# CAN0.net
KiCad netlist of a schematic drawn in Altium Designer
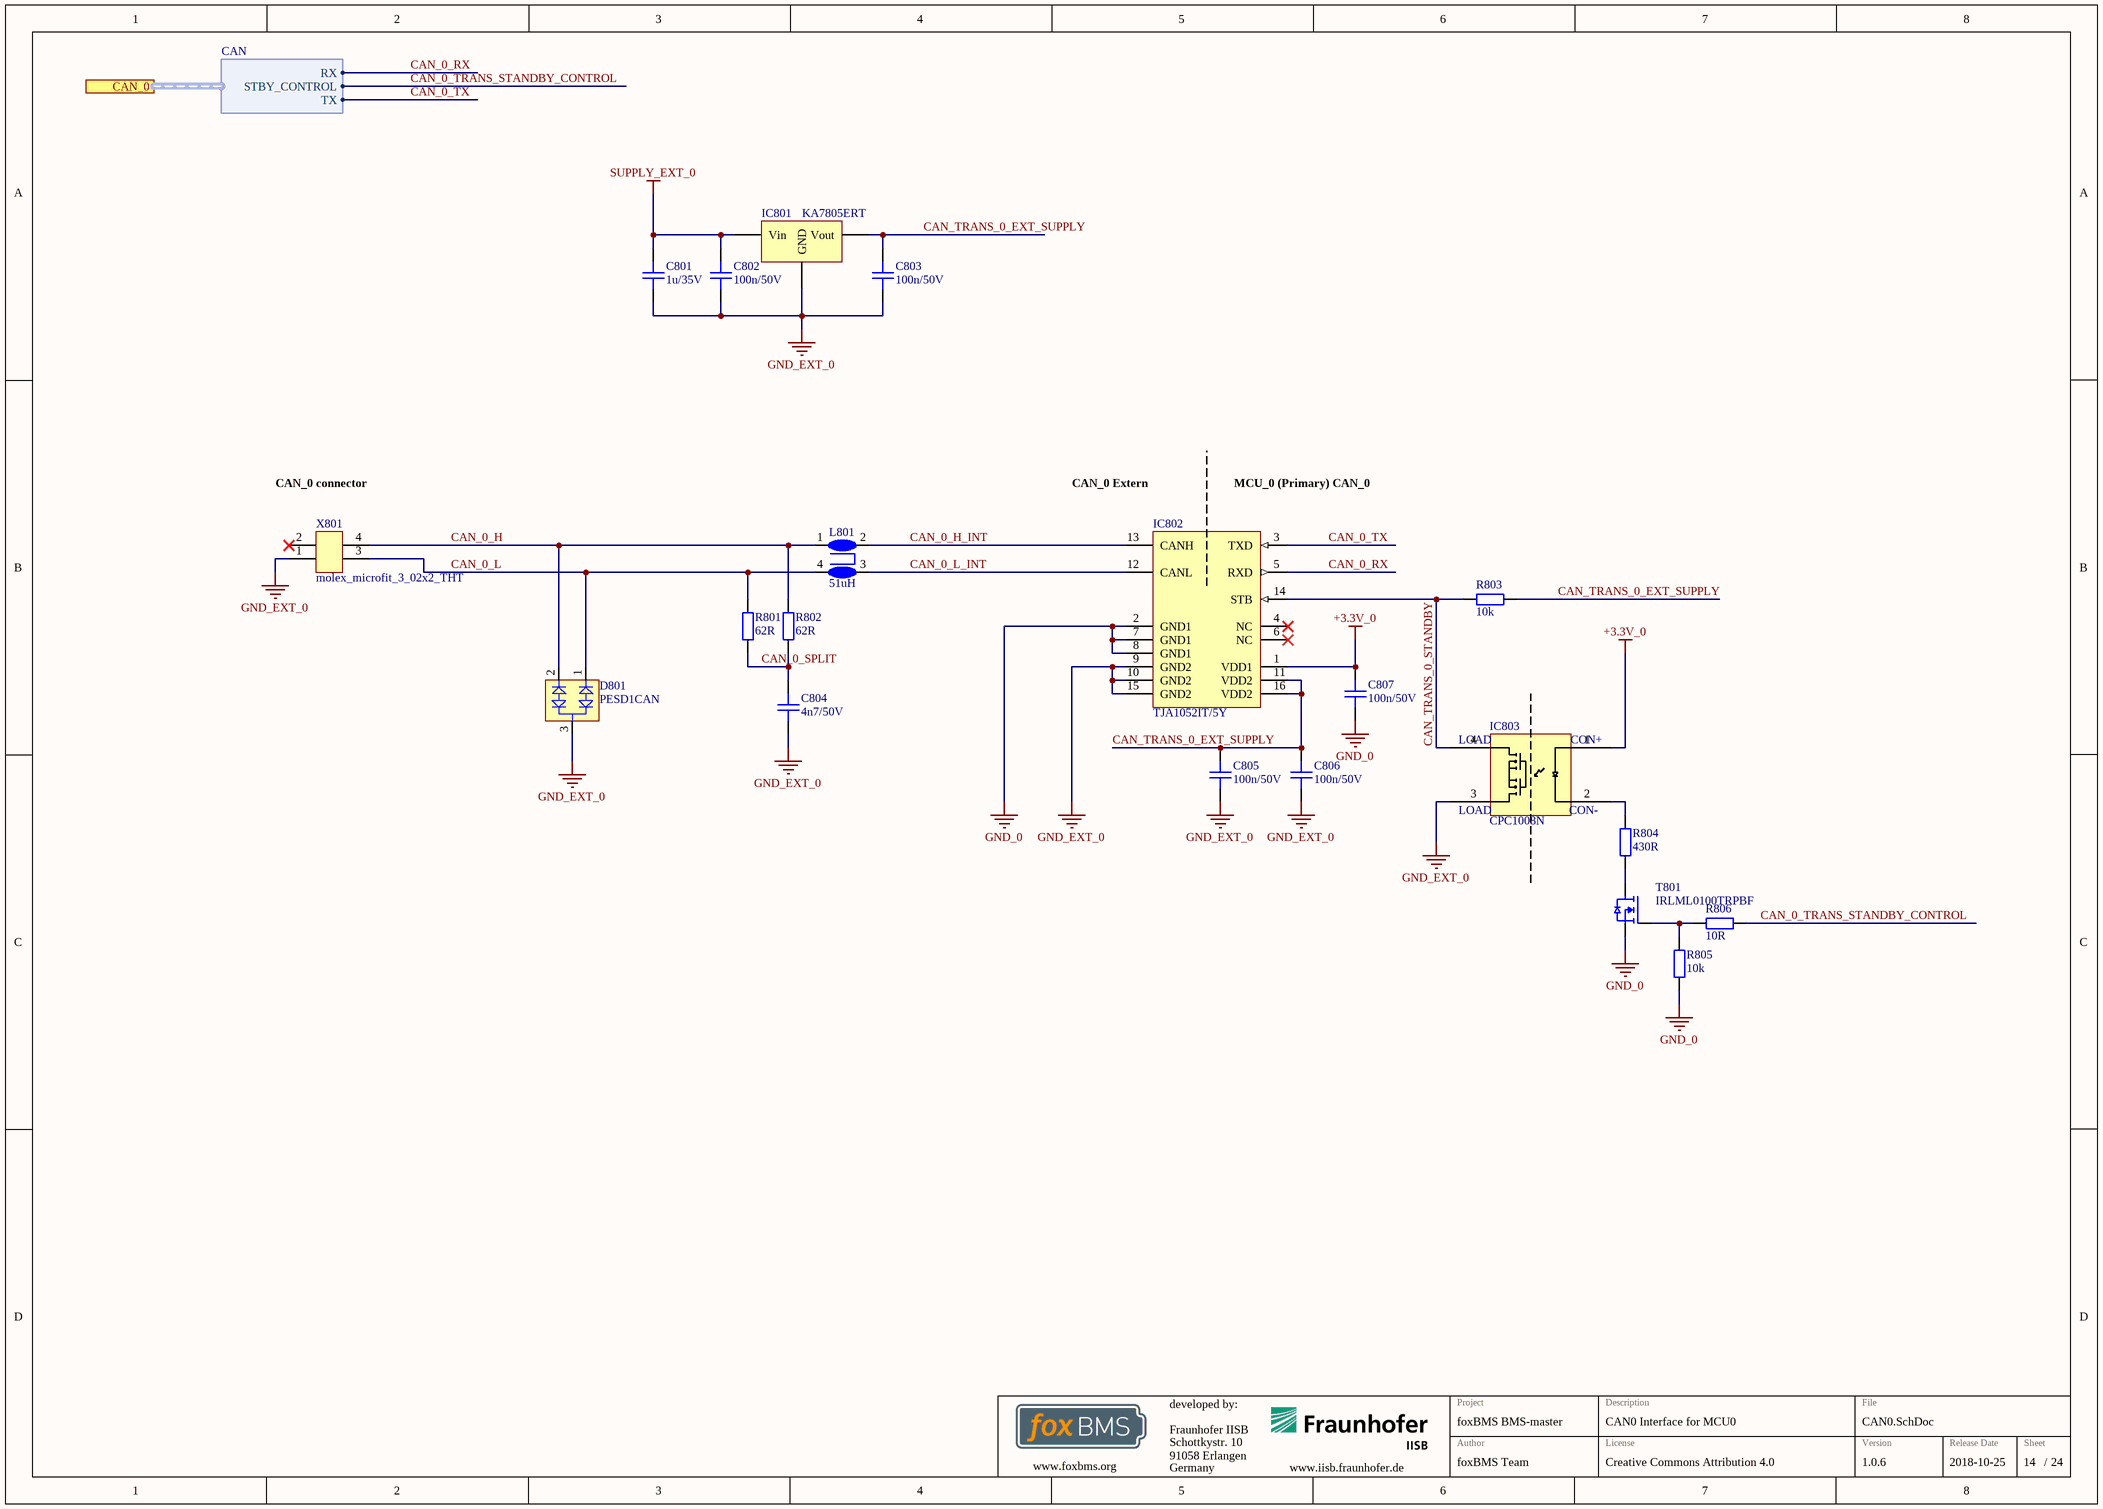
[diagram p0: CAN0.SchDoc]

(export (version "E")
  (design (tool "Eeschema 10.0.6"))
  (components
    (comp (ref "C801")
      (value "1u/35V")
      (footprint "CAPC1608X08N")
      (description "MLCC")
      (fields (field (name "PART NUMBER") "gen_C_ceramic_1u_35V_X7R_0603"))
      (libsource (lib "OE750") (part "C"))
    )
    (comp (ref "C802")
      (value "100n/50V")
      (footprint "CAPC1608X08N")
      (description "MLCC")
      (fields (field (name "PART NUMBER") "gen_C_ceramic_100n_50V_X7R_0603"))
      (libsource (lib "OE750") (part "C"))
    )
    (comp (ref "C803")
      (value "100n/50V")
      (footprint "CAPC1608X08N")
      (description "MLCC")
      (fields (field (name "PART NUMBER") "gen_C_ceramic_100n_50V_X7R_0603"))
      (libsource (lib "OE750") (part "C"))
    )
    (comp (ref "C804")
      (value "4n7/50V")
      (footprint "CAPC1608X08N")
      (description "MLCC")
      (fields (field (name "PART NUMBER") "gen_C_ceramic_4n7_50V_X7R_0603"))
      (libsource (lib "OE750") (part "C"))
    )
    (comp (ref "C805")
      (value "100n/50V")
      (footprint "CAPC1608X08N")
      (description "MLCC")
      (fields (field (name "PART NUMBER") "gen_C_ceramic_100n_50V_X7R_0603"))
      (libsource (lib "OE750") (part "C"))
    )
    (comp (ref "C806")
      (value "100n/50V")
      (footprint "CAPC1608X08N")
      (description "MLCC")
      (fields (field (name "PART NUMBER") "gen_C_ceramic_100n_50V_X7R_0603"))
      (libsource (lib "OE750") (part "C"))
    )
    (comp (ref "C807")
      (value "100n/50V")
      (footprint "CAPC1608X08N")
      (description "MLCC")
      (fields (field (name "PART NUMBER") "gen_C_ceramic_100n_50V_X7R_0603"))
      (libsource (lib "OE750") (part "C"))
    )
    (comp (ref "D801")
      (value "PESD1CAN")
      (footprint "NXP-SOT23-3_V")
      (description "CAN Bus ESD Protection Diode, 200 W, 24 V, -65 to 150 degC, 3-Pin SOT23, RoHS, Tape and Reel")
      (fields (field (name "MANUFACTURER") "NXP Semiconductors"))
      (libsource (lib "Altium Content Vault") (part "NXP-PESD1CAN-SOT23-3"))
    )
    (comp (ref "IC801")
      (value "KA7805ERT")
      (footprint "DPAK228P950X240-3N")
      (description "3-Terminal 1 A Positive Voltage Regulator")
      (fields (field (name "PART NUMBER") "KA7805ERTF") (field (name "MANUFACTURER") "Fairchild"))
      (libsource (lib "OE750") (part "KA7805ERT"))
    )
    (comp (ref "IC802")
      (value "TJA1052IT/5Y")
      (footprint "NXP-SOIC-16_L")
      (fields (field (name "MANUFACTURER") "NXPSemiconductors"))
      (libsource (lib "Altium Content Vault") (part "NXP-TJA1052IT-SOIC-16"))
    )
    (comp (ref "IC803")
      (value "CPC1008N")
      (footprint "SOP254P610X218-4N")
      (description "Single-Pole, Normally Open 4-Pin SOP OptoMOS Relay")
      (fields (field (name "MANUFACTURER") "CLARE"))
      (libsource (lib "OE750") (part "CPC1008N"))
    )
    (comp (ref "L801")
      (value "51uH")
      (footprint "B82789C0/S0")
      (description "Common Mode Choke")
      (fields (field (name "PART NUMBER") "B82789N") (field (name "MANUFACTURER") "EPCOS / TDK"))
      (libsource (lib "OE750") (part "L_CM"))
    )
    (comp (ref "R801")
      (value "62R")
      (footprint "RESC1608X05N")
      (description "SMD Resistor 62R 0603")
      (fields (field (name "PART NUMBER") "gen_R_62R_0603") (field (name "TOLERANCE") "1%"))
      (libsource (lib "OE750") (part "R"))
    )
    (comp (ref "R802")
      (value "62R")
      (footprint "RESC1608X05N")
      (description "SMD Resistor 62R 0603")
      (fields (field (name "PART NUMBER") "gen_R_62R_0603") (field (name "TOLERANCE") "1%"))
      (libsource (lib "OE750") (part "R"))
    )
    (comp (ref "R803")
      (value "10k")
      (footprint "RESC1608X05N")
      (description "SMD Resistor 10k 0603")
      (fields (field (name "PART NUMBER") "gen_R_10k_0603") (field (name "TOLERANCE") "1%"))
      (libsource (lib "OE750") (part "R"))
    )
    (comp (ref "R804")
      (value "430R")
      (footprint "RESC1608X05N")
      (description "SMD Resistor 430R 0603")
      (fields (field (name "PART NUMBER") "gen_R_430R_0603") (field (name "TOLERANCE") "1%"))
      (libsource (lib "OE750") (part "R"))
    )
    (comp (ref "R805")
      (value "10k")
      (footprint "RESC1608X05N")
      (description "SMD Resistor 10k 0603")
      (fields (field (name "PART NUMBER") "gen_R_10k_0603") (field (name "TOLERANCE") "1%"))
      (libsource (lib "OE750") (part "R"))
    )
    (comp (ref "R806")
      (value "10R")
      (footprint "RESC1608X05N")
      (description "SMD Resistor 10R 0603")
      (fields (field (name "PART NUMBER") "gen_R_10R_0603") (field (name "TOLERANCE") "1%"))
      (libsource (lib "OE750") (part "R"))
    )
    (comp (ref "T801")
      (value "IRLML0100TRPBF")
      (footprint "SOT95P237X110-3N")
      (description "MOSFET-Transistor, n-Kanal, 1.6 A, 100 V, 0.178 ohm, 10 V, 2.5 V")
      (fields (field (name "MANUFACTURER") "Infineon"))
      (libsource (lib "OE750") (part "NMOS"))
    )
    (comp (ref "X801")
      (value "molex_microfit_3_02x2_THT")
      (footprint "MOLEX_MICROFIT_02x2_THT")
      (fields (field (name "MANUFACTURER") "Molex"))
      (libsource (lib "OE750") (part "X2x2"))
    )
  )
  (nets
    (net (code "2") (name "+3.3V_0") (class "Default")
      (node (ref "C807") (pin "2") (pinfunction "2_2") (pintype "passive"))
      (node (ref "IC802") (pin "1") (pinfunction "VDD1_1") (pintype "power_in"))
      (node (ref "IC803") (pin "1") (pintype "passive"))
    )
    (net (code "3") (name "/CAN_0_H") (class "Default")
      (node (ref "D801") (pin "2") (pinfunction "K2_2") (pintype "passive"))
      (node (ref "L801") (pin "1") (pinfunction "1_1") (pintype "passive"))
      (node (ref "R802") (pin "2") (pinfunction "2_2") (pintype "passive"))
      (node (ref "X801") (pin "4") (pintype "passive"))
    )
    (net (code "4") (name "/CAN_0_H_INT") (class "Default")
      (node (ref "IC802") (pin "13") (pinfunction "CANH_13") (pintype "passive"))
      (node (ref "L801") (pin "2") (pinfunction "2_2") (pintype "passive"))
    )
    (net (code "5") (name "/CAN_0_L") (class "Default")
      (node (ref "D801") (pin "1") (pinfunction "K1_1") (pintype "passive"))
      (node (ref "L801") (pin "4") (pinfunction "4_4") (pintype "passive"))
      (node (ref "R801") (pin "1") (pinfunction "1_1") (pintype "passive"))
      (node (ref "X801") (pin "3") (pintype "passive"))
    )
    (net (code "6") (name "/CAN_0_L_INT") (class "Default")
      (node (ref "IC802") (pin "12") (pinfunction "CANL_12") (pintype "passive"))
      (node (ref "L801") (pin "3") (pinfunction "3_3") (pintype "passive"))
    )
    (net (code "7") (name "/CAN_0_RX") (class "Default")
      (node (ref "IC802") (pin "5") (pinfunction "RXD_5") (pintype "output"))
    )
    (net (code "8") (name "/CAN_0_SPLIT") (class "Default")
      (node (ref "C804") (pin "1") (pinfunction "1_1") (pintype "passive"))
      (node (ref "R801") (pin "2") (pinfunction "2_2") (pintype "passive"))
      (node (ref "R802") (pin "1") (pinfunction "1_1") (pintype "passive"))
    )
    (net (code "9") (name "/CAN_0_TRANS_STANDBY_CONTROL") (class "Default")
      (node (ref "R806") (pin "2") (pinfunction "2_2") (pintype "passive"))
    )
    (net (code "10") (name "/CAN_0_TX") (class "Default")
      (node (ref "IC802") (pin "3") (pinfunction "TXD_3") (pintype "input"))
    )
    (net (code "11") (name "/CAN_TRANS_0_EXT_SUPPLY") (class "Default")
      (node (ref "C803") (pin "2") (pinfunction "2_2") (pintype "passive"))
      (node (ref "C805") (pin "2") (pinfunction "2_2") (pintype "passive"))
      (node (ref "C806") (pin "2") (pinfunction "2_2") (pintype "passive"))
      (node (ref "IC801") (pin "3") (pinfunction "Vout_3") (pintype "power_in"))
      (node (ref "IC802") (pin "11") (pinfunction "VDD2_11") (pintype "power_in"))
      (node (ref "IC802") (pin "16") (pinfunction "VDD2_16") (pintype "power_in"))
      (node (ref "R803") (pin "1") (pinfunction "1_1") (pintype "passive"))
    )
    (net (code "12") (name "/CAN_TRANS_0_STANDBY") (class "Default")
      (node (ref "IC802") (pin "14") (pinfunction "STB_14") (pintype "input"))
      (node (ref "IC803") (pin "4") (pintype "passive"))
      (node (ref "R803") (pin "2") (pinfunction "2_2") (pintype "passive"))
    )
    (net (code "14") (name "GND_0") (class "Default")
      (node (ref "C807") (pin "1") (pinfunction "1_1") (pintype "passive"))
      (node (ref "IC802") (pin "2") (pinfunction "GND1_2") (pintype "power_in"))
      (node (ref "IC802") (pin "7") (pinfunction "GND1_7") (pintype "power_in"))
      (node (ref "IC802") (pin "8") (pinfunction "GND1_8") (pintype "power_in"))
      (node (ref "R805") (pin "2") (pinfunction "2_2") (pintype "passive"))
      (node (ref "T801") (pin "S") (pinfunction "S_S") (pintype "passive"))
    )
    (net (code "15") (name "GND_EXT_0") (class "Default")
      (node (ref "C801") (pin "1") (pinfunction "1_1") (pintype "passive"))
      (node (ref "C802") (pin "1") (pinfunction "1_1") (pintype "passive"))
      (node (ref "C803") (pin "1") (pinfunction "1_1") (pintype "passive"))
      (node (ref "C804") (pin "2") (pinfunction "2_2") (pintype "passive"))
      (node (ref "C805") (pin "1") (pinfunction "1_1") (pintype "passive"))
      (node (ref "C806") (pin "1") (pinfunction "1_1") (pintype "passive"))
      (node (ref "D801") (pin "3") (pinfunction "C_3") (pintype "passive"))
      (node (ref "IC801") (pin "2") (pinfunction "GND_2") (pintype "power_in"))
      (node (ref "IC802") (pin "10") (pinfunction "GND2_10") (pintype "power_in"))
      (node (ref "IC802") (pin "15") (pinfunction "GND2_15") (pintype "power_in"))
      (node (ref "IC802") (pin "9") (pinfunction "GND2_9") (pintype "power_in"))
      (node (ref "IC803") (pin "3") (pintype "passive"))
      (node (ref "X801") (pin "1") (pintype "passive"))
    )
    (net (code "16") (name "Net-(IC803-Pad2)") (class "Default")
      (node (ref "IC803") (pin "2") (pintype "power_in"))
      (node (ref "R804") (pin "1") (pinfunction "1_1") (pintype "passive"))
    )
    (net (code "17") (name "Net-(R804-Pad2)") (class "Default")
      (node (ref "R804") (pin "2") (pinfunction "2_2") (pintype "passive"))
      (node (ref "T801") (pin "D") (pinfunction "D_D") (pintype "passive"))
    )
    (net (code "18") (name "Net-(R805-Pad1)") (class "Default")
      (node (ref "R805") (pin "1") (pinfunction "1_1") (pintype "passive"))
      (node (ref "R806") (pin "1") (pinfunction "1_1") (pintype "passive"))
      (node (ref "T801") (pin "G") (pinfunction "G_G") (pintype "passive"))
    )
    (net (code "19") (name "SUPPLY_EXT_0") (class "Default")
      (node (ref "C801") (pin "2") (pinfunction "2_2") (pintype "passive"))
      (node (ref "C802") (pin "2") (pinfunction "2_2") (pintype "passive"))
      (node (ref "IC801") (pin "1") (pinfunction "Vin_1") (pintype "power_in"))
    )
    (net (code "20") (name "unconnected-(IC802-NC-Pad4)") (class "Default")
      (node (ref "IC802") (pin "4") (pinfunction "NC_4") (pintype "passive+no_connect"))
    )
    (net (code "21") (name "unconnected-(IC802-NC-Pad6)") (class "Default")
      (node (ref "IC802") (pin "6") (pinfunction "NC_6") (pintype "passive+no_connect"))
    )
    (net (code "22") (name "unconnected-(X801-Pad2)") (class "Default")
      (node (ref "X801") (pin "2") (pintype "passive+no_connect"))
    )
  )
)
